# rotboard.net
KiCad netlist of a schematic drawn in Altium Designer
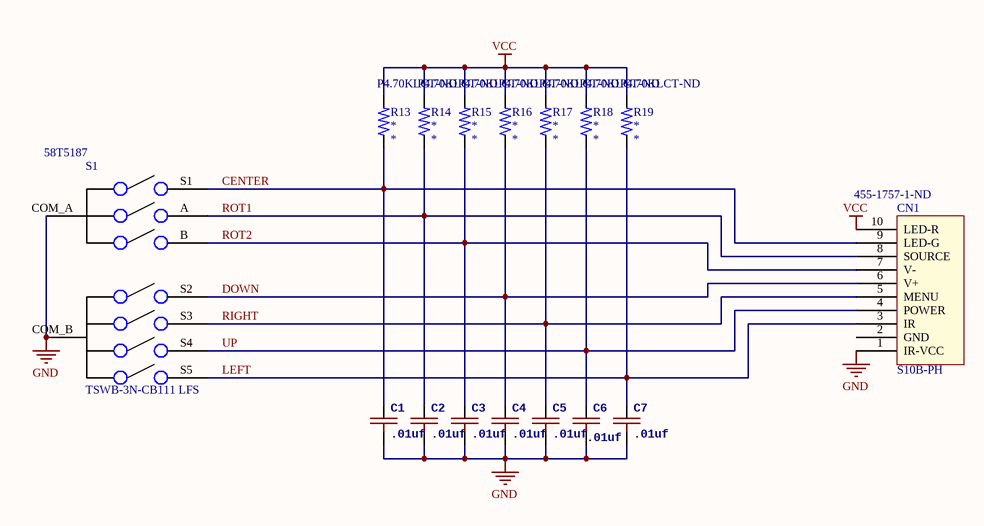
[diagram p0: rotboard.SchDoc]

(export (version "E")
  (design (tool "Eeschema 10.0.6"))
  (components
    (comp (ref "C1") (value ".01uf") (footprint "0402C") (libsource (lib "adafruit") (part "C-USC0402")))
    (comp (ref "C2") (value ".01uf") (footprint "0402C") (libsource (lib "adafruit") (part "C-USC0402")))
    (comp (ref "C3") (value ".01uf") (footprint "0402C") (libsource (lib "adafruit") (part "C-USC0402")))
    (comp (ref "C4") (value ".01uf") (footprint "0402C") (libsource (lib "adafruit") (part "C-USC0402")))
    (comp (ref "C5") (value ".01uf") (footprint "0402C") (libsource (lib "adafruit") (part "C-USC0402")))
    (comp (ref "C6") (value ".01uf") (footprint "0402C") (libsource (lib "adafruit") (part "C-USC0402")))
    (comp (ref "C7") (value ".01uf") (footprint "0402C") (libsource (lib "adafruit") (part "C-USC0402")))
    (comp (ref "CN1")
      (value "S10B-PH")
      (footprint "ezLCD405:PH-SM4")
      (fields (field (name "SUPPLIER PART NUMBER 1") "455-1757-1-ND"))
      (libsource (lib "ezLCD405") (part "S10B-PH"))
    )
    (comp (ref "R13")
      (value "*")
      (footprint "R0402")
      (description "Resistor 0805")
      (fields (field (name "ALTIUM_VALUE") "*") (field (name "SUPPLIER PART NUMBER 1") "P4.70KLCT-ND"))
      (libsource (lib "EarthLib1") (part "R-US_R0805"))
    )
    (comp (ref "R14")
      (value "*")
      (footprint "R0402")
      (description "Resistor 0805")
      (fields (field (name "ALTIUM_VALUE") "*") (field (name "SUPPLIER PART NUMBER 1") "P4.70KLCT-ND"))
      (libsource (lib "EarthLib1") (part "R-US_R0805"))
    )
    (comp (ref "R15")
      (value "*")
      (footprint "R0402")
      (description "Resistor 0805")
      (fields (field (name "ALTIUM_VALUE") "*") (field (name "SUPPLIER PART NUMBER 1") "P4.70KLCT-ND"))
      (libsource (lib "EarthLib1") (part "R-US_R0805"))
    )
    (comp (ref "R16")
      (value "*")
      (footprint "R0402")
      (description "Resistor 0805")
      (fields (field (name "ALTIUM_VALUE") "*") (field (name "SUPPLIER PART NUMBER 1") "P4.70KLCT-ND"))
      (libsource (lib "EarthLib1") (part "R-US_R0805"))
    )
    (comp (ref "R17")
      (value "*")
      (footprint "R0402")
      (description "Resistor 0805")
      (fields (field (name "ALTIUM_VALUE") "*") (field (name "SUPPLIER PART NUMBER 1") "P4.70KLCT-ND"))
      (libsource (lib "EarthLib1") (part "R-US_R0805"))
    )
    (comp (ref "R18")
      (value "*")
      (footprint "R0402")
      (description "Resistor 0805")
      (fields (field (name "ALTIUM_VALUE") "*") (field (name "SUPPLIER PART NUMBER 1") "P4.70KLCT-ND"))
      (libsource (lib "EarthLib1") (part "R-US_R0805"))
    )
    (comp (ref "R19")
      (value "*")
      (footprint "R0402")
      (description "Resistor 0805")
      (fields (field (name "ALTIUM_VALUE") "*") (field (name "SUPPLIER PART NUMBER 1") "P4.70KLCT-ND"))
      (libsource (lib "EarthLib1") (part "R-US_R0805"))
    )
    (comp (ref "S1")
      (value "TSWB-3N-CB111 LFS")
      (footprint "ezLCD405:TSWB-3N-CB111 LFS")
      (fields (field (name "SUPPLIER PART NUMBER 1") "58T5187"))
      (libsource (lib "ezLCD405") (part "TSWB-3N-CB111 LFS"))
    )
  )
  (nets
    (net (code "1") (name "/CENTER") (class "Default")
      (node (ref "C1") (pin "1") (pinfunction "1_1") (pintype "passive"))
      (node (ref "CN1") (pin "9") (pinfunction "LED-G_9") (pintype "passive"))
      (node (ref "R13") (pin "1") (pinfunction "1_1") (pintype "passive"))
      (node (ref "S1") (pin "S1") (pinfunction "S1_S1") (pintype "passive"))
    )
    (net (code "2") (name "/DOWN") (class "Default")
      (node (ref "C4") (pin "1") (pinfunction "1_1") (pintype "passive"))
      (node (ref "CN1") (pin "6") (pinfunction "V+_6") (pintype "passive"))
      (node (ref "R16") (pin "1") (pinfunction "1_1") (pintype "passive"))
      (node (ref "S1") (pin "S2") (pinfunction "S2_S2") (pintype "passive"))
    )
    (net (code "3") (name "/LEFT") (class "Default")
      (node (ref "C7") (pin "1") (pinfunction "1_1") (pintype "passive"))
      (node (ref "CN1") (pin "3") (pinfunction "IR_3") (pintype "passive"))
      (node (ref "R19") (pin "1") (pinfunction "1_1") (pintype "passive"))
      (node (ref "S1") (pin "S5") (pinfunction "S5_S5") (pintype "passive"))
    )
    (net (code "4") (name "/RIGHT") (class "Default")
      (node (ref "C5") (pin "1") (pinfunction "1_1") (pintype "passive"))
      (node (ref "CN1") (pin "5") (pinfunction "MENU_5") (pintype "passive"))
      (node (ref "R17") (pin "1") (pinfunction "1_1") (pintype "passive"))
      (node (ref "S1") (pin "S3") (pinfunction "S3_S3") (pintype "passive"))
    )
    (net (code "5") (name "/ROT1") (class "Default")
      (node (ref "C2") (pin "1") (pinfunction "1_1") (pintype "passive"))
      (node (ref "CN1") (pin "8") (pinfunction "SOURCE_8") (pintype "passive"))
      (node (ref "R14") (pin "1") (pinfunction "1_1") (pintype "passive"))
      (node (ref "S1") (pin "A") (pinfunction "A_A") (pintype "passive"))
    )
    (net (code "6") (name "/ROT2") (class "Default")
      (node (ref "C3") (pin "1") (pinfunction "1_1") (pintype "passive"))
      (node (ref "CN1") (pin "7") (pinfunction "V-_7") (pintype "passive"))
      (node (ref "R15") (pin "1") (pinfunction "1_1") (pintype "passive"))
      (node (ref "S1") (pin "B") (pinfunction "B_B") (pintype "passive"))
    )
    (net (code "7") (name "/UP") (class "Default")
      (node (ref "C6") (pin "1") (pinfunction "1_1") (pintype "passive"))
      (node (ref "CN1") (pin "4") (pinfunction "POWER_4") (pintype "passive"))
      (node (ref "R18") (pin "1") (pinfunction "1_1") (pintype "passive"))
      (node (ref "S1") (pin "S4") (pinfunction "S4_S4") (pintype "passive"))
    )
    (net (code "8") (name "GND") (class "Default")
      (node (ref "C1") (pin "2") (pinfunction "2_2") (pintype "passive"))
      (node (ref "C2") (pin "2") (pinfunction "2_2") (pintype "passive"))
      (node (ref "C3") (pin "2") (pinfunction "2_2") (pintype "passive"))
      (node (ref "C4") (pin "2") (pinfunction "2_2") (pintype "passive"))
      (node (ref "C5") (pin "2") (pinfunction "2_2") (pintype "passive"))
      (node (ref "C6") (pin "2") (pinfunction "2_2") (pintype "passive"))
      (node (ref "C7") (pin "2") (pinfunction "2_2") (pintype "passive"))
      (node (ref "CN1") (pin "1") (pinfunction "IR-VCC_1") (pintype "passive"))
      (node (ref "S1") (pin "COM_A") (pinfunction "COM_A_COM_A") (pintype "passive"))
      (node (ref "S1") (pin "COM_B") (pinfunction "COM_B_COM_B") (pintype "passive"))
    )
    (net (code "9") (name "VCC") (class "Default")
      (node (ref "CN1") (pin "10") (pinfunction "LED-R_10") (pintype "passive"))
      (node (ref "R13") (pin "2") (pinfunction "2_2") (pintype "passive"))
      (node (ref "R14") (pin "2") (pinfunction "2_2") (pintype "passive"))
      (node (ref "R15") (pin "2") (pinfunction "2_2") (pintype "passive"))
      (node (ref "R16") (pin "2") (pinfunction "2_2") (pintype "passive"))
      (node (ref "R17") (pin "2") (pinfunction "2_2") (pintype "passive"))
      (node (ref "R18") (pin "2") (pinfunction "2_2") (pintype "passive"))
      (node (ref "R19") (pin "2") (pinfunction "2_2") (pintype "passive"))
    )
    (net (code "10") (name "unconnected-(CN1-GND-Pad2)") (class "Default")
      (node (ref "CN1") (pin "2") (pinfunction "GND_2") (pintype "passive"))
    )
  )
)
